# Markise-Relais.net
KiCad netlist of a schematic drawn in EAGLE
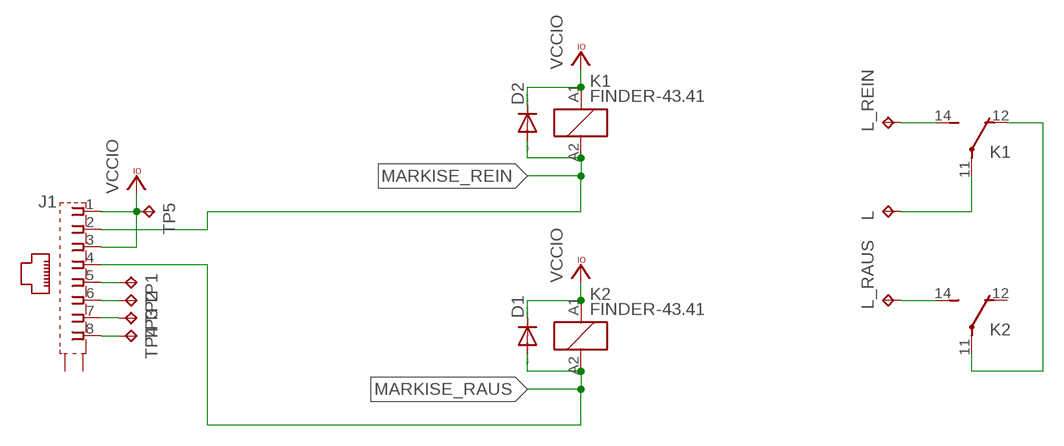
[diagram p0: schematic, sheet 1]

(export (version "E")
  (design (tool "Eeschema 10.0.6"))
  (components
    (comp (ref "D1")
      (value "DIODE-D-7.5")
      (footprint "eagle-import:D-7.5")
      (libsource (lib "eagle-import") (part "DIODE-D-7.5"))
    )
    (comp (ref "D2")
      (value "DIODE-D-7.5")
      (footprint "eagle-import:D-7.5")
      (libsource (lib "eagle-import") (part "DIODE-D-7.5"))
    )
    (comp (ref "J1")
      (value "555141-1")
      (footprint "eagle-import:555153-1")
      (libsource (lib "eagle-import") (part "555141-1"))
    )
    (comp (ref "K1")
      (value "FINDER-43.41")
      (footprint "eagle-import:FINDER-43.41")
      (libsource (lib "eagle-import") (part "FINDER-43.41"))
    )
    (comp (ref "K2")
      (value "FINDER-43.41")
      (footprint "eagle-import:FINDER-43.41")
      (libsource (lib "eagle-import") (part "FINDER-43.41"))
    )
    (comp (ref "L")
      (value "TPPAD1-20Y")
      (footprint "eagle-import:P1-20Y")
      (libsource (lib "eagle-import") (part "TPPAD1-20Y"))
    )
    (comp (ref "L_RAUS")
      (value "TPPAD1-20Y")
      (footprint "eagle-import:P1-20Y")
      (libsource (lib "eagle-import") (part "TPPAD1-20Y"))
    )
    (comp (ref "L_REIN")
      (value "TPPAD1-20Y")
      (footprint "eagle-import:P1-20Y")
      (libsource (lib "eagle-import") (part "TPPAD1-20Y"))
    )
    (comp (ref "TP1")
      (value "TPPAD1-13")
      (footprint "eagle-import:P1-13")
      (libsource (lib "eagle-import") (part "TPPAD1-13"))
    )
    (comp (ref "TP2")
      (value "TPPAD1-13")
      (footprint "eagle-import:P1-13")
      (libsource (lib "eagle-import") (part "TPPAD1-13"))
    )
    (comp (ref "TP3")
      (value "TPPAD1-13")
      (footprint "eagle-import:P1-13")
      (libsource (lib "eagle-import") (part "TPPAD1-13"))
    )
    (comp (ref "TP4")
      (value "TPPAD1-13")
      (footprint "eagle-import:P1-13")
      (libsource (lib "eagle-import") (part "TPPAD1-13"))
    )
    (comp (ref "TP5")
      (value "TPPAD1-13")
      (footprint "eagle-import:P1-13")
      (libsource (lib "eagle-import") (part "TPPAD1-13"))
    )
  )
  (nets
    (net (code "1") (name "MARKISE_RAUS") (class "Default")
      (node (ref "D1") (pin "A") (pinfunction "A_A") (pintype "passive"))
      (node (ref "J1") (pin "4") (pinfunction "4_4") (pintype "passive"))
      (node (ref "K2") (pin "A2") (pinfunction "2_A2") (pintype "passive"))
    )
    (net (code "2") (name "MARKISE_REIN") (class "Default")
      (node (ref "D2") (pin "A") (pinfunction "A_A") (pintype "passive"))
      (node (ref "J1") (pin "2") (pinfunction "2_2") (pintype "passive"))
      (node (ref "K1") (pin "A2") (pinfunction "2_A2") (pintype "passive"))
    )
    (net (code "3") (name "Net-(J1-Pad5)") (class "Default")
      (node (ref "J1") (pin "5") (pinfunction "5_5") (pintype "passive"))
      (node (ref "TP1") (pin "TP") (pinfunction "TP_TP") (pintype "input"))
    )
    (net (code "4") (name "Net-(J1-Pad6)") (class "Default")
      (node (ref "J1") (pin "6") (pinfunction "6_6") (pintype "passive"))
      (node (ref "TP2") (pin "TP") (pinfunction "TP_TP") (pintype "input"))
    )
    (net (code "5") (name "Net-(J1-Pad7)") (class "Default")
      (node (ref "J1") (pin "7") (pinfunction "7_7") (pintype "passive"))
      (node (ref "TP3") (pin "TP") (pinfunction "TP_TP") (pintype "input"))
    )
    (net (code "6") (name "Net-(J1-Pad8)") (class "Default")
      (node (ref "J1") (pin "8") (pinfunction "8_8") (pintype "passive"))
      (node (ref "TP4") (pin "TP") (pinfunction "TP_TP") (pintype "input"))
    )
    (net (code "7") (name "Net-(K1A-O)") (class "Default")
      (node (ref "K1") (pin "12") (pinfunction "O_12") (pintype "passive"))
      (node (ref "K2") (pin "11") (pinfunction "P_11") (pintype "passive"))
    )
    (net (code "8") (name "Net-(K1A-P)") (class "Default")
      (node (ref "K1") (pin "11") (pinfunction "P_11") (pintype "passive"))
      (node (ref "L") (pin "TP") (pinfunction "TP_TP") (pintype "input"))
    )
    (net (code "9") (name "Net-(K1A-S)") (class "Default")
      (node (ref "K1") (pin "14") (pinfunction "S_14") (pintype "passive"))
      (node (ref "L_REIN") (pin "TP") (pinfunction "TP_TP") (pintype "input"))
    )
    (net (code "10") (name "Net-(K2A-S)") (class "Default")
      (node (ref "K2") (pin "14") (pinfunction "S_14") (pintype "passive"))
      (node (ref "L_RAUS") (pin "TP") (pinfunction "TP_TP") (pintype "input"))
    )
    (net (code "11") (name "VCCIO") (class "Default")
      (node (ref "D1") (pin "C") (pinfunction "C_C") (pintype "passive"))
      (node (ref "D2") (pin "C") (pinfunction "C_C") (pintype "passive"))
      (node (ref "J1") (pin "1") (pinfunction "1_1") (pintype "passive"))
      (node (ref "J1") (pin "3") (pinfunction "3_3") (pintype "passive"))
      (node (ref "K1") (pin "A1") (pinfunction "1_A1") (pintype "passive"))
      (node (ref "K2") (pin "A1") (pinfunction "1_A1") (pintype "passive"))
      (node (ref "TP5") (pin "TP") (pinfunction "TP_TP") (pintype "input"))
    )
    (net (code "12") (name "unconnected-(J1-S1-PadG1)") (class "Default")
      (node (ref "J1") (pin "G1") (pinfunction "S1_G1") (pintype "passive"))
    )
    (net (code "13") (name "unconnected-(J1-S2-PadG2)") (class "Default")
      (node (ref "J1") (pin "G2") (pinfunction "S2_G2") (pintype "passive"))
    )
    (net (code "14") (name "unconnected-(K2A-O-Pad12)") (class "Default")
      (node (ref "K2") (pin "12") (pinfunction "O_12") (pintype "passive"))
    )
  )
)
